# MGMEZZ04_LoopBack.net
KiCad netlist of a schematic drawn in Altium Designer
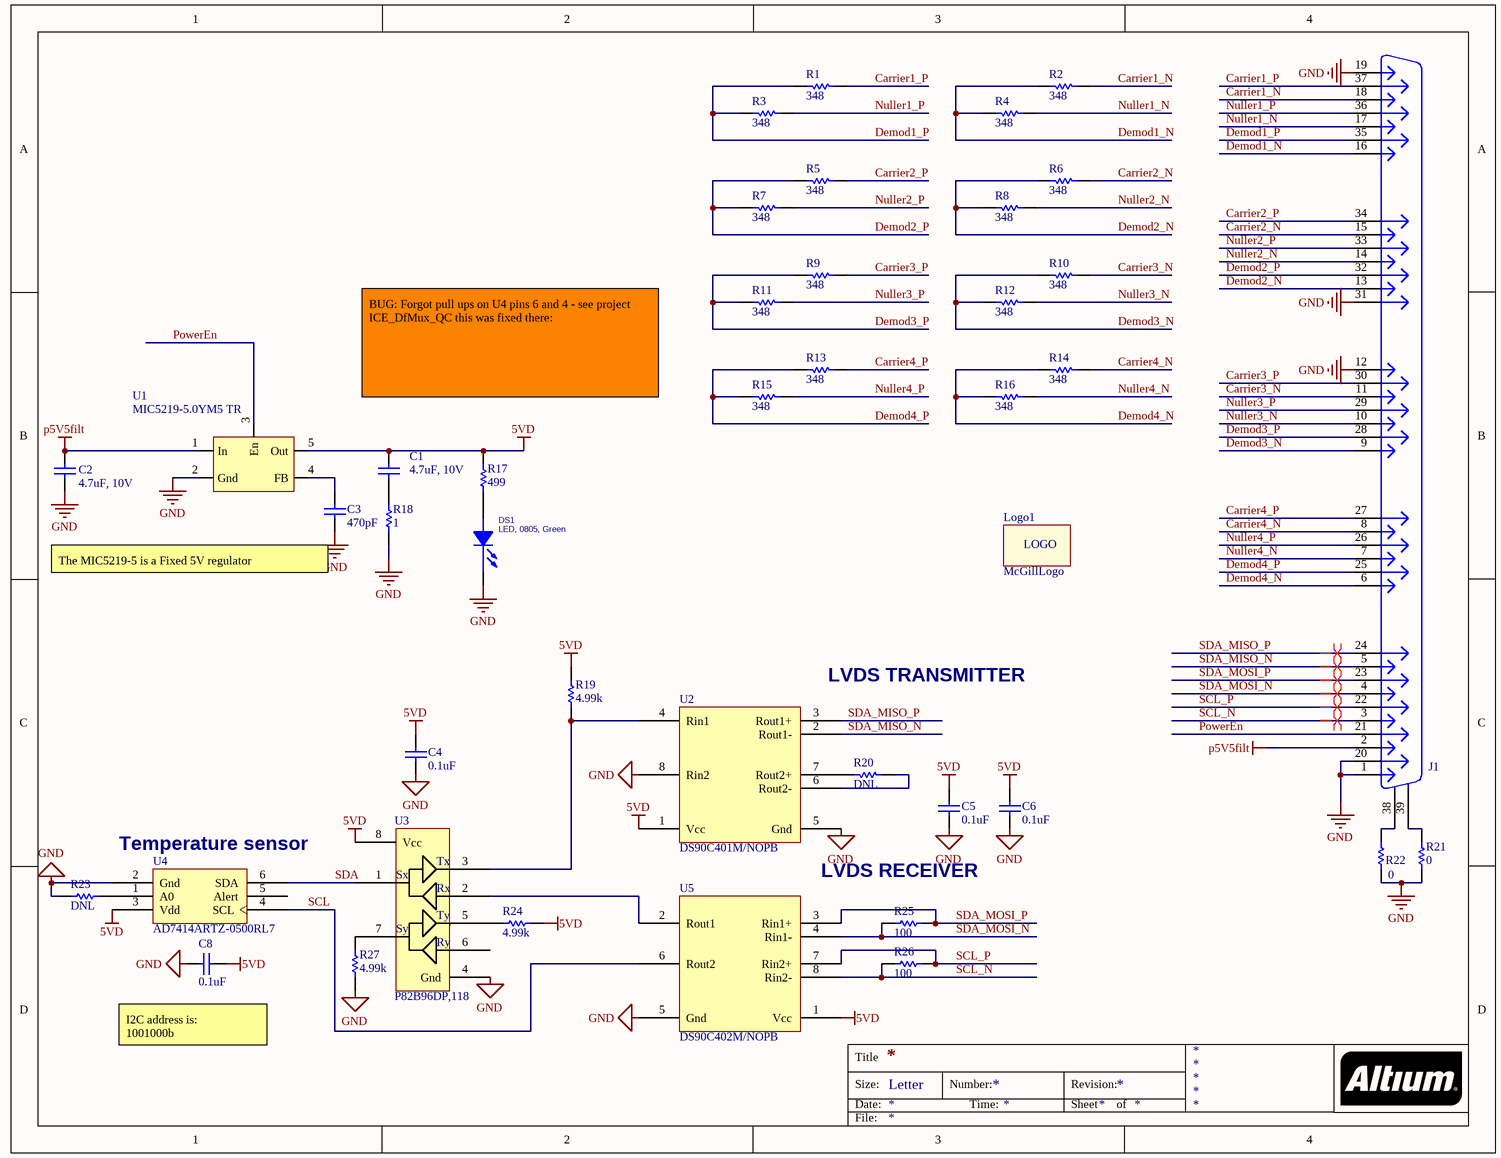
[diagram p0: MGMEZZ04_LoopBack.SchDoc]

(export (version "E")
  (design (tool "Eeschema 10.0.6"))
  (components
    (comp (ref "C1")
      (value "4.7uF, 10V")
      (footprint "0805")
      (description "Capacitor, Ceramic, 0805")
      (fields
        (field (name "MANUFACTURER") "Taiyo Yuden")
        (field (name "MANUFACTURER PART NUMBER") "LMK212BJ475KD-T")
      )
      (libsource (lib "MGMEZZ04") (part "CAP 0805"))
    )
    (comp (ref "C2")
      (value "4.7uF, 10V")
      (footprint "0805")
      (description "Capacitor, Ceramic, 0805")
      (fields
        (field (name "MANUFACTURER") "Taiyo Yuden")
        (field (name "MANUFACTURER PART NUMBER") "LMK212BJ475KD-T")
      )
      (libsource (lib "MGMEZZ04") (part "CAP 0805"))
    )
    (comp (ref "C3")
      (value "470pF")
      (footprint "0603")
      (description "Capacitor, Ceramic, 0603")
      (fields
        (field (name "MANUFACTURER") "Kemet")
        (field (name "MANUFACTURER PART NUMBER") "C0603C471K5RACTU")
      )
      (libsource (lib "MiniSquidCtrl") (part "Cap0603"))
    )
    (comp (ref "C4")
      (value "0.1uF")
      (footprint "0603")
      (description "Capacitor, Ceramic, 0603")
      (fields
        (field (name "MANUFACTURER") "Kemet")
        (field (name "MANUFACTURER PART NUMBER") "C0603C104K4RACTU")
      )
      (libsource (lib "MiniSquidCtrl") (part "Cap0603"))
    )
    (comp (ref "C5")
      (value "0.1uF")
      (footprint "0603")
      (description "Capacitor, Ceramic, 0603")
      (fields
        (field (name "MANUFACTURER") "Kemet")
        (field (name "MANUFACTURER PART NUMBER") "C0603C104K4RACTU")
      )
      (libsource (lib "MiniSquidCtrl") (part "Cap0603"))
    )
    (comp (ref "C6")
      (value "0.1uF")
      (footprint "0603")
      (description "Capacitor, Ceramic, 0603")
      (fields
        (field (name "MANUFACTURER") "Kemet")
        (field (name "MANUFACTURER PART NUMBER") "C0603C104K4RACTU")
      )
      (libsource (lib "MiniSquidCtrl") (part "Cap0603"))
    )
    (comp (ref "C8")
      (value "0.1uF")
      (footprint "0603")
      (description "Capacitor, Ceramic, 0603")
      (fields
        (field (name "MANUFACTURER") "Kemet")
        (field (name "MANUFACTURER PART NUMBER") "C0603C104K4RACTU")
      )
      (libsource (lib "MiniSquidCtrl") (part "Cap0603"))
    )
    (comp (ref "DS1")
      (value "LED, 0805, Green")
      (description "LED GREEN CLEAR 0805 SMD")
      (fields
        (field (name "MANUFACTURER") "Lite-On Inc")
        (field (name "MANUFACTURER PART NUMBER") "LTST-C170GKT")
      )
      (libsource (lib "MGMEZZ04_Loopback") (part "LED"))
    )
    (comp (ref "J1")
      (value "DB37M")
      (footprint "DSUB37-M")
      (fields (field (name "MANUFACTURER") "Norcomp") (field (name "MANUFACTURER PART NUMBER") "182-37ME-ND"))
      (libsource (lib "MGMEZZ04_Loopback") (part "DB37M"))
    )
    (comp (ref "Logo1")
      (value "McGillLogo")
      (footprint "McGillLogo1")
      (description "Silkscreen Logo")
      (fields (field (name "MANUFACTURER") "McGill"))
      (libsource (lib "MGMEZZ04_Loopback") (part "Logo"))
    )
    (comp (ref "R1")
      (value "348")
      (footprint "0603")
      (description "RES 0603")
      (fields
        (field (name "MANUFACTURER") "Yageo")
        (field (name "MANUFACTURER PART NUMBER") "RC0603FR-07348RL")
      )
      (libsource (lib "MiniSquidCtrl") (part "Res0603"))
    )
    (comp (ref "R2")
      (value "348")
      (footprint "0603")
      (description "RES 0603")
      (fields
        (field (name "MANUFACTURER") "Yageo")
        (field (name "MANUFACTURER PART NUMBER") "RC0603FR-07348RL")
      )
      (libsource (lib "MiniSquidCtrl") (part "Res0603"))
    )
    (comp (ref "R3")
      (value "348")
      (footprint "0603")
      (description "RES 0603")
      (fields
        (field (name "MANUFACTURER") "Yageo")
        (field (name "MANUFACTURER PART NUMBER") "RC0603FR-07348RL")
      )
      (libsource (lib "MiniSquidCtrl") (part "Res0603"))
    )
    (comp (ref "R4")
      (value "348")
      (footprint "0603")
      (description "RES 0603")
      (fields
        (field (name "MANUFACTURER") "Yageo")
        (field (name "MANUFACTURER PART NUMBER") "RC0603FR-07348RL")
      )
      (libsource (lib "MiniSquidCtrl") (part "Res0603"))
    )
    (comp (ref "R5")
      (value "348")
      (footprint "0603")
      (description "RES 0603")
      (fields
        (field (name "MANUFACTURER") "Yageo")
        (field (name "MANUFACTURER PART NUMBER") "RC0603FR-07348RL")
      )
      (libsource (lib "MiniSquidCtrl") (part "Res0603"))
    )
    (comp (ref "R6")
      (value "348")
      (footprint "0603")
      (description "RES 0603")
      (fields
        (field (name "MANUFACTURER") "Yageo")
        (field (name "MANUFACTURER PART NUMBER") "RC0603FR-07348RL")
      )
      (libsource (lib "MiniSquidCtrl") (part "Res0603"))
    )
    (comp (ref "R7")
      (value "348")
      (footprint "0603")
      (description "RES 0603")
      (fields
        (field (name "MANUFACTURER") "Yageo")
        (field (name "MANUFACTURER PART NUMBER") "RC0603FR-07348RL")
      )
      (libsource (lib "MiniSquidCtrl") (part "Res0603"))
    )
    (comp (ref "R8")
      (value "348")
      (footprint "0603")
      (description "RES 0603")
      (fields
        (field (name "MANUFACTURER") "Yageo")
        (field (name "MANUFACTURER PART NUMBER") "RC0603FR-07348RL")
      )
      (libsource (lib "MiniSquidCtrl") (part "Res0603"))
    )
    (comp (ref "R9")
      (value "348")
      (footprint "0603")
      (description "RES 0603")
      (fields
        (field (name "MANUFACTURER") "Yageo")
        (field (name "MANUFACTURER PART NUMBER") "RC0603FR-07348RL")
      )
      (libsource (lib "MiniSquidCtrl") (part "Res0603"))
    )
    (comp (ref "R10")
      (value "348")
      (footprint "0603")
      (description "RES 0603")
      (fields
        (field (name "MANUFACTURER") "Yageo")
        (field (name "MANUFACTURER PART NUMBER") "RC0603FR-07348RL")
      )
      (libsource (lib "MiniSquidCtrl") (part "Res0603"))
    )
    (comp (ref "R11")
      (value "348")
      (footprint "0603")
      (description "RES 0603")
      (fields
        (field (name "MANUFACTURER") "Yageo")
        (field (name "MANUFACTURER PART NUMBER") "RC0603FR-07348RL")
      )
      (libsource (lib "MiniSquidCtrl") (part "Res0603"))
    )
    (comp (ref "R12")
      (value "348")
      (footprint "0603")
      (description "RES 0603")
      (fields
        (field (name "MANUFACTURER") "Yageo")
        (field (name "MANUFACTURER PART NUMBER") "RC0603FR-07348RL")
      )
      (libsource (lib "MiniSquidCtrl") (part "Res0603"))
    )
    (comp (ref "R13")
      (value "348")
      (footprint "0603")
      (description "RES 0603")
      (fields
        (field (name "MANUFACTURER") "Yageo")
        (field (name "MANUFACTURER PART NUMBER") "RC0603FR-07348RL")
      )
      (libsource (lib "MiniSquidCtrl") (part "Res0603"))
    )
    (comp (ref "R14")
      (value "348")
      (footprint "0603")
      (description "RES 0603")
      (fields
        (field (name "MANUFACTURER") "Yageo")
        (field (name "MANUFACTURER PART NUMBER") "RC0603FR-07348RL")
      )
      (libsource (lib "MiniSquidCtrl") (part "Res0603"))
    )
    (comp (ref "R15")
      (value "348")
      (footprint "0603")
      (description "RES 0603")
      (fields
        (field (name "MANUFACTURER") "Yageo")
        (field (name "MANUFACTURER PART NUMBER") "RC0603FR-07348RL")
      )
      (libsource (lib "MiniSquidCtrl") (part "Res0603"))
    )
    (comp (ref "R16")
      (value "348")
      (footprint "0603")
      (description "RES 0603")
      (fields
        (field (name "MANUFACTURER") "Yageo")
        (field (name "MANUFACTURER PART NUMBER") "RC0603FR-07348RL")
      )
      (libsource (lib "MiniSquidCtrl") (part "Res0603"))
    )
    (comp (ref "R17")
      (value "499")
      (footprint "0603")
      (description "RES 0603")
      (fields
        (field (name "MANUFACTURER") "Vishay Dale")
        (field (name "MANUFACTURER PART NUMBER") "CRCW0603499RFKEA")
      )
      (libsource (lib "MiniSquidCtrl") (part "RES 0603"))
    )
    (comp (ref "R18")
      (value "1")
      (footprint "0603")
      (description "RES 0603")
      (fields
        (field (name "MANUFACTURER") "Vishay Dale")
        (field (name "MANUFACTURER PART NUMBER") "CRCW06031R00FKEA")
      )
      (libsource (lib "MiniSquidCtrl") (part "Res0603"))
    )
    (comp (ref "R19")
      (value "4.99k")
      (footprint "0603")
      (description "RES 0603")
      (fields
        (field (name "MANUFACTURER") "Yageo")
        (field (name "MANUFACTURER PART NUMBER") "RC0603FR-074K99L")
      )
      (libsource (lib "MiniSquidCtrl") (part "Res0603"))
    )
    (comp (ref "R20")
      (value "DNL")
      (footprint "0603")
      (description "RES 0603")
      (fields
        (field (name "MANUFACTURER") "Generic")
        (field (name "MANUFACTURER PART NUMBER") "e.g CRCW0603 series")
      )
      (libsource (lib "MiniSquidCtrl") (part "Res0603"))
    )
    (comp (ref "R21")
      (value "0")
      (footprint "0603")
      (description "RES 0603")
      (fields
        (field (name "MANUFACTURER") "Yageo")
        (field (name "MANUFACTURER PART NUMBER") "RC0603JR-070RL")
      )
      (libsource (lib "MiniSquidCtrl") (part "RES 0603"))
    )
    (comp (ref "R22")
      (value "0")
      (footprint "0603")
      (description "RES 0603")
      (fields
        (field (name "MANUFACTURER") "Yageo")
        (field (name "MANUFACTURER PART NUMBER") "RC0603JR-070RL")
      )
      (libsource (lib "MiniSquidCtrl") (part "RES 0603"))
    )
    (comp (ref "R23")
      (value "DNL")
      (footprint "0603")
      (description "RES 0603")
      (fields
        (field (name "MANUFACTURER") "Generic")
        (field (name "MANUFACTURER PART NUMBER") "e.g CRCW0603 series")
      )
      (libsource (lib "MiniSquidCtrl") (part "Res0603"))
    )
    (comp (ref "R24")
      (value "4.99k")
      (footprint "0603")
      (description "RES 0603")
      (fields
        (field (name "MANUFACTURER") "Yageo")
        (field (name "MANUFACTURER PART NUMBER") "RC0603FR-074K99L")
      )
      (libsource (lib "MiniSquidCtrl") (part "Res0603"))
    )
    (comp (ref "R25")
      (value "100")
      (footprint "0603")
      (description "RES 0603")
      (fields
        (field (name "MANUFACTURER") "Yageo")
        (field (name "MANUFACTURER PART NUMBER") "C0603FR-07100RL")
      )
      (libsource (lib "MiniSquidCtrl") (part "RES 0603"))
    )
    (comp (ref "R26")
      (value "100")
      (footprint "0603")
      (description "RES 0603")
      (fields
        (field (name "MANUFACTURER") "Yageo")
        (field (name "MANUFACTURER PART NUMBER") "C0603FR-07100RL")
      )
      (libsource (lib "MiniSquidCtrl") (part "RES 0603"))
    )
    (comp (ref "R27")
      (value "4.99k")
      (footprint "0603")
      (description "RES 0603")
      (fields
        (field (name "MANUFACTURER") "Yageo")
        (field (name "MANUFACTURER PART NUMBER") "RC0603FR-074K99L")
      )
      (libsource (lib "MiniSquidCtrl") (part "Res0603"))
    )
    (comp (ref "U1")
      (value "MIC5219-5.0YM5 TR")
      (footprint "SOT23-5")
      (description "Adjustable 30uVrms noise 400mA regulator")
      (fields (field (name "MANUFACTURER") "Micrel Inc"))
      (libsource (lib "MGMEZZ04") (part "TPS73601DBVR"))
    )
    (comp (ref "U2")
      (value "DS90C401M/NOPB")
      (footprint "SO8")
      (description "IC DRV LVDS DUAL DIFF SGNL 8SOIC")
      (fields
        (field (name "MANUFACTURER") "Texas Instruments")
        (field (name "MANUFACTURER PART NUMBER") "DS90C401MX/NOPB")
      )
      (libsource (lib "MiniSquidCtrl") (part "DS90C401M/NOPB"))
    )
    (comp (ref "U3")
      (value "P82B96DP,118")
      (footprint "MSOP8-P82B96")
      (description "IC DUAL BI-DIR BUS BUFFER 8-TSSOP")
      (libsource (lib "MiniSquidCtrl") (part "P82B96"))
    )
    (comp (ref "U4")
      (value "AD7414ARTZ-0500RL7")
      (footprint "SOT23-6")
      (description "Digital Temperature Sensor, 11-Bit, +/-2 Degree Accurate")
      (fields (field (name "MANUFACTURER") "Analog Devices"))
      (libsource (lib "MiniSquidCtrl") (part "AD7414ARTZ-0500RL7"))
    )
    (comp (ref "U5")
      (value "DS90C402M/NOPB")
      (footprint "SO8")
      (description "IC REC LVDS DUAL DIFF SGNL 8SOIC")
      (fields
        (field (name "MANUFACTURER") "Texas Instruments")
        (field (name "MANUFACTURER PART NUMBER") "DS90C402MX/NOPB")
      )
      (libsource (lib "MiniSquidCtrl") (part "DS90C402M/NOPB"))
    )
  )
  (nets
    (net (code "1") (name "/Carrier1_N") (class "Default")
      (node (ref "J1") (pin "18") (pinfunction "18_18") (pintype "passive"))
      (node (ref "R2") (pin "2") (pinfunction "2_2") (pintype "passive"))
    )
    (net (code "2") (name "/Carrier1_P") (class "Default")
      (node (ref "J1") (pin "37") (pinfunction "37_37") (pintype "passive"))
      (node (ref "R1") (pin "2") (pinfunction "2_2") (pintype "passive"))
    )
    (net (code "3") (name "/Carrier2_N") (class "Default")
      (node (ref "J1") (pin "15") (pinfunction "15_15") (pintype "passive"))
      (node (ref "R6") (pin "2") (pinfunction "2_2") (pintype "passive"))
    )
    (net (code "4") (name "/Carrier2_P") (class "Default")
      (node (ref "J1") (pin "34") (pinfunction "34_34") (pintype "passive"))
      (node (ref "R5") (pin "2") (pinfunction "2_2") (pintype "passive"))
    )
    (net (code "5") (name "/Carrier3_N") (class "Default")
      (node (ref "J1") (pin "11") (pinfunction "11_11") (pintype "passive"))
      (node (ref "R10") (pin "2") (pinfunction "2_2") (pintype "passive"))
    )
    (net (code "6") (name "/Carrier3_P") (class "Default")
      (node (ref "J1") (pin "30") (pinfunction "30_30") (pintype "passive"))
      (node (ref "R9") (pin "2") (pinfunction "2_2") (pintype "passive"))
    )
    (net (code "7") (name "/Carrier4_N") (class "Default")
      (node (ref "J1") (pin "8") (pinfunction "8_8") (pintype "passive"))
      (node (ref "R14") (pin "2") (pinfunction "2_2") (pintype "passive"))
    )
    (net (code "8") (name "/Carrier4_P") (class "Default")
      (node (ref "J1") (pin "27") (pinfunction "27_27") (pintype "passive"))
      (node (ref "R13") (pin "2") (pinfunction "2_2") (pintype "passive"))
    )
    (net (code "9") (name "/Demod1_N") (class "Default")
      (node (ref "J1") (pin "16") (pinfunction "16_16") (pintype "passive"))
      (node (ref "R2") (pin "1") (pinfunction "1_1") (pintype "passive"))
      (node (ref "R4") (pin "1") (pinfunction "1_1") (pintype "passive"))
    )
    (net (code "10") (name "/Demod1_P") (class "Default")
      (node (ref "J1") (pin "35") (pinfunction "35_35") (pintype "passive"))
      (node (ref "R1") (pin "1") (pinfunction "1_1") (pintype "passive"))
      (node (ref "R3") (pin "1") (pinfunction "1_1") (pintype "passive"))
    )
    (net (code "11") (name "/Demod2_N") (class "Default")
      (node (ref "J1") (pin "13") (pinfunction "13_13") (pintype "passive"))
      (node (ref "R6") (pin "1") (pinfunction "1_1") (pintype "passive"))
      (node (ref "R8") (pin "1") (pinfunction "1_1") (pintype "passive"))
    )
    (net (code "12") (name "/Demod2_P") (class "Default")
      (node (ref "J1") (pin "32") (pinfunction "32_32") (pintype "passive"))
      (node (ref "R5") (pin "1") (pinfunction "1_1") (pintype "passive"))
      (node (ref "R7") (pin "1") (pinfunction "1_1") (pintype "passive"))
    )
    (net (code "13") (name "/Demod3_N") (class "Default")
      (node (ref "J1") (pin "9") (pinfunction "9_9") (pintype "passive"))
      (node (ref "R10") (pin "1") (pinfunction "1_1") (pintype "passive"))
      (node (ref "R12") (pin "1") (pinfunction "1_1") (pintype "passive"))
    )
    (net (code "14") (name "/Demod3_P") (class "Default")
      (node (ref "J1") (pin "28") (pinfunction "28_28") (pintype "passive"))
      (node (ref "R11") (pin "1") (pinfunction "1_1") (pintype "passive"))
      (node (ref "R9") (pin "1") (pinfunction "1_1") (pintype "passive"))
    )
    (net (code "15") (name "/Demod4_N") (class "Default")
      (node (ref "J1") (pin "6") (pinfunction "6_6") (pintype "passive"))
      (node (ref "R14") (pin "1") (pinfunction "1_1") (pintype "passive"))
      (node (ref "R16") (pin "1") (pinfunction "1_1") (pintype "passive"))
    )
    (net (code "16") (name "/Demod4_P") (class "Default")
      (node (ref "J1") (pin "25") (pinfunction "25_25") (pintype "passive"))
      (node (ref "R13") (pin "1") (pinfunction "1_1") (pintype "passive"))
      (node (ref "R15") (pin "1") (pinfunction "1_1") (pintype "passive"))
    )
    (net (code "17") (name "/Nuller1_N") (class "Default")
      (node (ref "J1") (pin "17") (pinfunction "17_17") (pintype "passive"))
      (node (ref "R4") (pin "2") (pinfunction "2_2") (pintype "passive"))
    )
    (net (code "18") (name "/Nuller1_P") (class "Default")
      (node (ref "J1") (pin "36") (pinfunction "36_36") (pintype "passive"))
      (node (ref "R3") (pin "2") (pinfunction "2_2") (pintype "passive"))
    )
    (net (code "19") (name "/Nuller2_N") (class "Default")
      (node (ref "J1") (pin "14") (pinfunction "14_14") (pintype "passive"))
      (node (ref "R8") (pin "2") (pinfunction "2_2") (pintype "passive"))
    )
    (net (code "20") (name "/Nuller2_P") (class "Default")
      (node (ref "J1") (pin "33") (pinfunction "33_33") (pintype "passive"))
      (node (ref "R7") (pin "2") (pinfunction "2_2") (pintype "passive"))
    )
    (net (code "21") (name "/Nuller3_N") (class "Default")
      (node (ref "J1") (pin "10") (pinfunction "10_10") (pintype "passive"))
      (node (ref "R12") (pin "2") (pinfunction "2_2") (pintype "passive"))
    )
    (net (code "22") (name "/Nuller3_P") (class "Default")
      (node (ref "J1") (pin "29") (pinfunction "29_29") (pintype "passive"))
      (node (ref "R11") (pin "2") (pinfunction "2_2") (pintype "passive"))
    )
    (net (code "23") (name "/Nuller4_N") (class "Default")
      (node (ref "J1") (pin "7") (pinfunction "7_7") (pintype "passive"))
      (node (ref "R16") (pin "2") (pinfunction "2_2") (pintype "passive"))
    )
    (net (code "24") (name "/Nuller4_P") (class "Default")
      (node (ref "J1") (pin "26") (pinfunction "26_26") (pintype "passive"))
      (node (ref "R15") (pin "2") (pinfunction "2_2") (pintype "passive"))
    )
    (net (code "25") (name "/PowerEn") (class "Default")
      (node (ref "J1") (pin "21") (pinfunction "21_21") (pintype "passive"))
      (node (ref "U1") (pin "3") (pinfunction "En_3") (pintype "passive"))
    )
    (net (code "26") (name "/SCL") (class "Default")
      (node (ref "U4") (pin "4") (pinfunction "SCL_4") (pintype "passive"))
      (node (ref "U5") (pin "6") (pinfunction "Rout2_6") (pintype "passive"))
    )
    (net (code "27") (name "/SCL_N") (class "Default")
      (node (ref "J1") (pin "3") (pinfunction "3_3") (pintype "passive"))
      (node (ref "R26") (pin "1") (pinfunction "1_1") (pintype "passive"))
      (node (ref "U5") (pin "8") (pinfunction "Rin2-_8") (pintype "passive"))
    )
    (net (code "28") (name "/SCL_P") (class "Default")
      (node (ref "J1") (pin "22") (pinfunction "22_22") (pintype "passive"))
      (node (ref "R26") (pin "2") (pinfunction "2_2") (pintype "passive"))
      (node (ref "U5") (pin "7") (pinfunction "Rin2+_7") (pintype "passive"))
    )
    (net (code "29") (name "/SDA") (class "Default")
      (node (ref "U3") (pin "1") (pinfunction "Sx_1") (pintype "passive"))
      (node (ref "U4") (pin "6") (pinfunction "SDA_6") (pintype "passive"))
    )
    (net (code "30") (name "/SDA_MISO_N") (class "Default")
      (node (ref "J1") (pin "5") (pinfunction "5_5") (pintype "passive"))
      (node (ref "U2") (pin "2") (pinfunction "Rout1-_2") (pintype "passive"))
    )
    (net (code "31") (name "/SDA_MISO_P") (class "Default")
      (node (ref "J1") (pin "24") (pinfunction "24_24") (pintype "passive"))
      (node (ref "U2") (pin "3") (pinfunction "Rout1+_3") (pintype "passive"))
    )
    (net (code "32") (name "/SDA_MOSI_N") (class "Default")
      (node (ref "J1") (pin "4") (pinfunction "4_4") (pintype "passive"))
      (node (ref "R25") (pin "1") (pinfunction "1_1") (pintype "passive"))
      (node (ref "U5") (pin "4") (pinfunction "Rin1-_4") (pintype "passive"))
    )
    (net (code "33") (name "/SDA_MOSI_P") (class "Default")
      (node (ref "J1") (pin "23") (pinfunction "23_23") (pintype "passive"))
      (node (ref "R25") (pin "2") (pinfunction "2_2") (pintype "passive"))
      (node (ref "U5") (pin "3") (pinfunction "Rin1+_3") (pintype "passive"))
    )
    (net (code "34") (name "5VD") (class "Default")
      (node (ref "C1") (pin "2") (pinfunction "2_2") (pintype "passive"))
      (node (ref "C4") (pin "2") (pinfunction "2_2") (pintype "passive"))
      (node (ref "C5") (pin "2") (pinfunction "2_2") (pintype "passive"))
      (node (ref "C6") (pin "2") (pinfunction "2_2") (pintype "passive"))
      (node (ref "C8") (pin "2") (pinfunction "2_2") (pintype "passive"))
      (node (ref "R17") (pin "1") (pinfunction "1_1") (pintype "passive"))
      (node (ref "R19") (pin "2") (pinfunction "2_2") (pintype "passive"))
      (node (ref "R24") (pin "2") (pinfunction "2_2") (pintype "passive"))
      (node (ref "U1") (pin "5") (pinfunction "Out_5") (pintype "passive"))
      (node (ref "U2") (pin "1") (pinfunction "Vcc_1") (pintype "passive"))
      (node (ref "U3") (pin "8") (pinfunction "Vcc_8") (pintype "passive"))
      (node (ref "U4") (pin "3") (pinfunction "Vdd_3") (pintype "power_in"))
      (node (ref "U5") (pin "1") (pinfunction "Vcc_1") (pintype "passive"))
    )
    (net (code "35") (name "GND") (class "Default")
      (node (ref "C2") (pin "1") (pinfunction "1_1") (pintype "passive"))
      (node (ref "C3") (pin "1") (pinfunction "1_1") (pintype "passive"))
      (node (ref "C4") (pin "1") (pinfunction "1_1") (pintype "passive"))
      (node (ref "C5") (pin "1") (pinfunction "1_1") (pintype "passive"))
      (node (ref "C6") (pin "1") (pinfunction "1_1") (pintype "passive"))
      (node (ref "C8") (pin "1") (pinfunction "1_1") (pintype "passive"))
      (node (ref "DS1") (pin "2") (pinfunction "CATHODE_2") (pintype "passive"))
      (node (ref "J1") (pin "1") (pinfunction "1_1") (pintype "passive"))
      (node (ref "J1") (pin "12") (pinfunction "12_12") (pintype "passive"))
      (node (ref "J1") (pin "19") (pinfunction "19_19") (pintype "passive"))
      (node (ref "J1") (pin "20") (pinfunction "20_20") (pintype "passive"))
      (node (ref "J1") (pin "31") (pinfunction "31_31") (pintype "passive"))
      (node (ref "R18") (pin "1") (pinfunction "1_1") (pintype "passive"))
      (node (ref "R21") (pin "2") (pinfunction "2_2") (pintype "passive"))
      (node (ref "R22") (pin "1") (pinfunction "1_1") (pintype "passive"))
      (node (ref "R23") (pin "2") (pinfunction "2_2") (pintype "passive"))
      (node (ref "R27") (pin "1") (pinfunction "1_1") (pintype "passive"))
      (node (ref "U1") (pin "2") (pinfunction "Gnd_2") (pintype "passive"))
      (node (ref "U2") (pin "5") (pinfunction "Gnd_5") (pintype "passive"))
      (node (ref "U2") (pin "8") (pinfunction "Rin2_8") (pintype "passive"))
      (node (ref "U3") (pin "4") (pinfunction "Gnd_4") (pintype "passive"))
      (node (ref "U4") (pin "2") (pinfunction "Gnd_2") (pintype "passive"))
      (node (ref "U5") (pin "5") (pinfunction "Gnd_5") (pintype "passive"))
    )
    (net (code "36") (name "Net-(C1-Pad1)") (class "Default")
      (node (ref "C1") (pin "1") (pinfunction "1_1") (pintype "passive"))
      (node (ref "R18") (pin "2") (pinfunction "2_2") (pintype "passive"))
    )
    (net (code "37") (name "Net-(DS1-ANODE)") (class "Default")
      (node (ref "DS1") (pin "1") (pinfunction "ANODE_1") (pintype "passive"))
      (node (ref "R17") (pin "2") (pinfunction "2_2") (pintype "passive"))
    )
    (net (code "38") (name "Net-(J1-MH1)") (class "Default")
      (node (ref "J1") (pin "38") (pinfunction "MH1_38") (pintype "passive"))
      (node (ref "R22") (pin "2") (pinfunction "2_2") (pintype "passive"))
    )
    (net (code "39") (name "Net-(J1-MH2)") (class "Default")
      (node (ref "J1") (pin "39") (pinfunction "MH2_39") (pintype "passive"))
      (node (ref "R21") (pin "1") (pinfunction "1_1") (pintype "passive"))
    )
    (net (code "40") (name "Net-(U1-FB)") (class "Default")
      (node (ref "C3") (pin "2") (pinfunction "2_2") (pintype "passive"))
      (node (ref "U1") (pin "4") (pinfunction "FB_4") (pintype "passive"))
    )
    (net (code "41") (name "Net-(U2-Rin1)") (class "Default")
      (node (ref "R19") (pin "1") (pinfunction "1_1") (pintype "passive"))
      (node (ref "U2") (pin "4") (pinfunction "Rin1_4") (pintype "passive"))
      (node (ref "U3") (pin "3") (pinfunction "Tx_3") (pintype "passive"))
    )
    (net (code "42") (name "Net-(U2-Rout2+)") (class "Default")
      (node (ref "R20") (pin "2") (pinfunction "2_2") (pintype "passive"))
      (node (ref "U2") (pin "7") (pinfunction "Rout2+_7") (pintype "passive"))
    )
    (net (code "43") (name "Net-(U2-Rout2-)") (class "Default")
      (node (ref "R20") (pin "1") (pinfunction "1_1") (pintype "passive"))
      (node (ref "U2") (pin "6") (pinfunction "Rout2-_6") (pintype "passive"))
    )
    (net (code "44") (name "Net-(U3-Rx)") (class "Default")
      (node (ref "U3") (pin "2") (pinfunction "Rx_2") (pintype "passive"))
      (node (ref "U5") (pin "2") (pinfunction "Rout1_2") (pintype "passive"))
    )
    (net (code "45") (name "Net-(U3-Sy)") (class "Default")
      (node (ref "R27") (pin "2") (pinfunction "2_2") (pintype "passive"))
      (node (ref "U3") (pin "7") (pinfunction "Sy_7") (pintype "passive"))
    )
    (net (code "46") (name "Net-(U3-Ty)") (class "Default")
      (node (ref "R24") (pin "1") (pinfunction "1_1") (pintype "passive"))
      (node (ref "U3") (pin "5") (pinfunction "Ty_5") (pintype "passive"))
    )
    (net (code "47") (name "Net-(U4-A0)") (class "Default")
      (node (ref "R23") (pin "1") (pinfunction "1_1") (pintype "passive"))
      (node (ref "U4") (pin "1") (pinfunction "A0_1") (pintype "power_in"))
    )
    (net (code "48") (name "p5V5filt") (class "Default")
      (node (ref "C2") (pin "2") (pinfunction "2_2") (pintype "passive"))
      (node (ref "J1") (pin "2") (pinfunction "2_2") (pintype "passive"))
      (node (ref "U1") (pin "1") (pinfunction "In_1") (pintype "passive"))
    )
    (net (code "49") (name "unconnected-(U3-Ry-Pad6)") (class "Default")
      (node (ref "U3") (pin "6") (pinfunction "Ry_6") (pintype "passive"))
    )
    (net (code "50") (name "unconnected-(U4-Alert-Pad5)") (class "Default")
      (node (ref "U4") (pin "5") (pinfunction "Alert_5") (pintype "passive"))
    )
  )
)
